# Wrap030_Memory.net
KiCad netlist of a schematic drawn in EAGLE
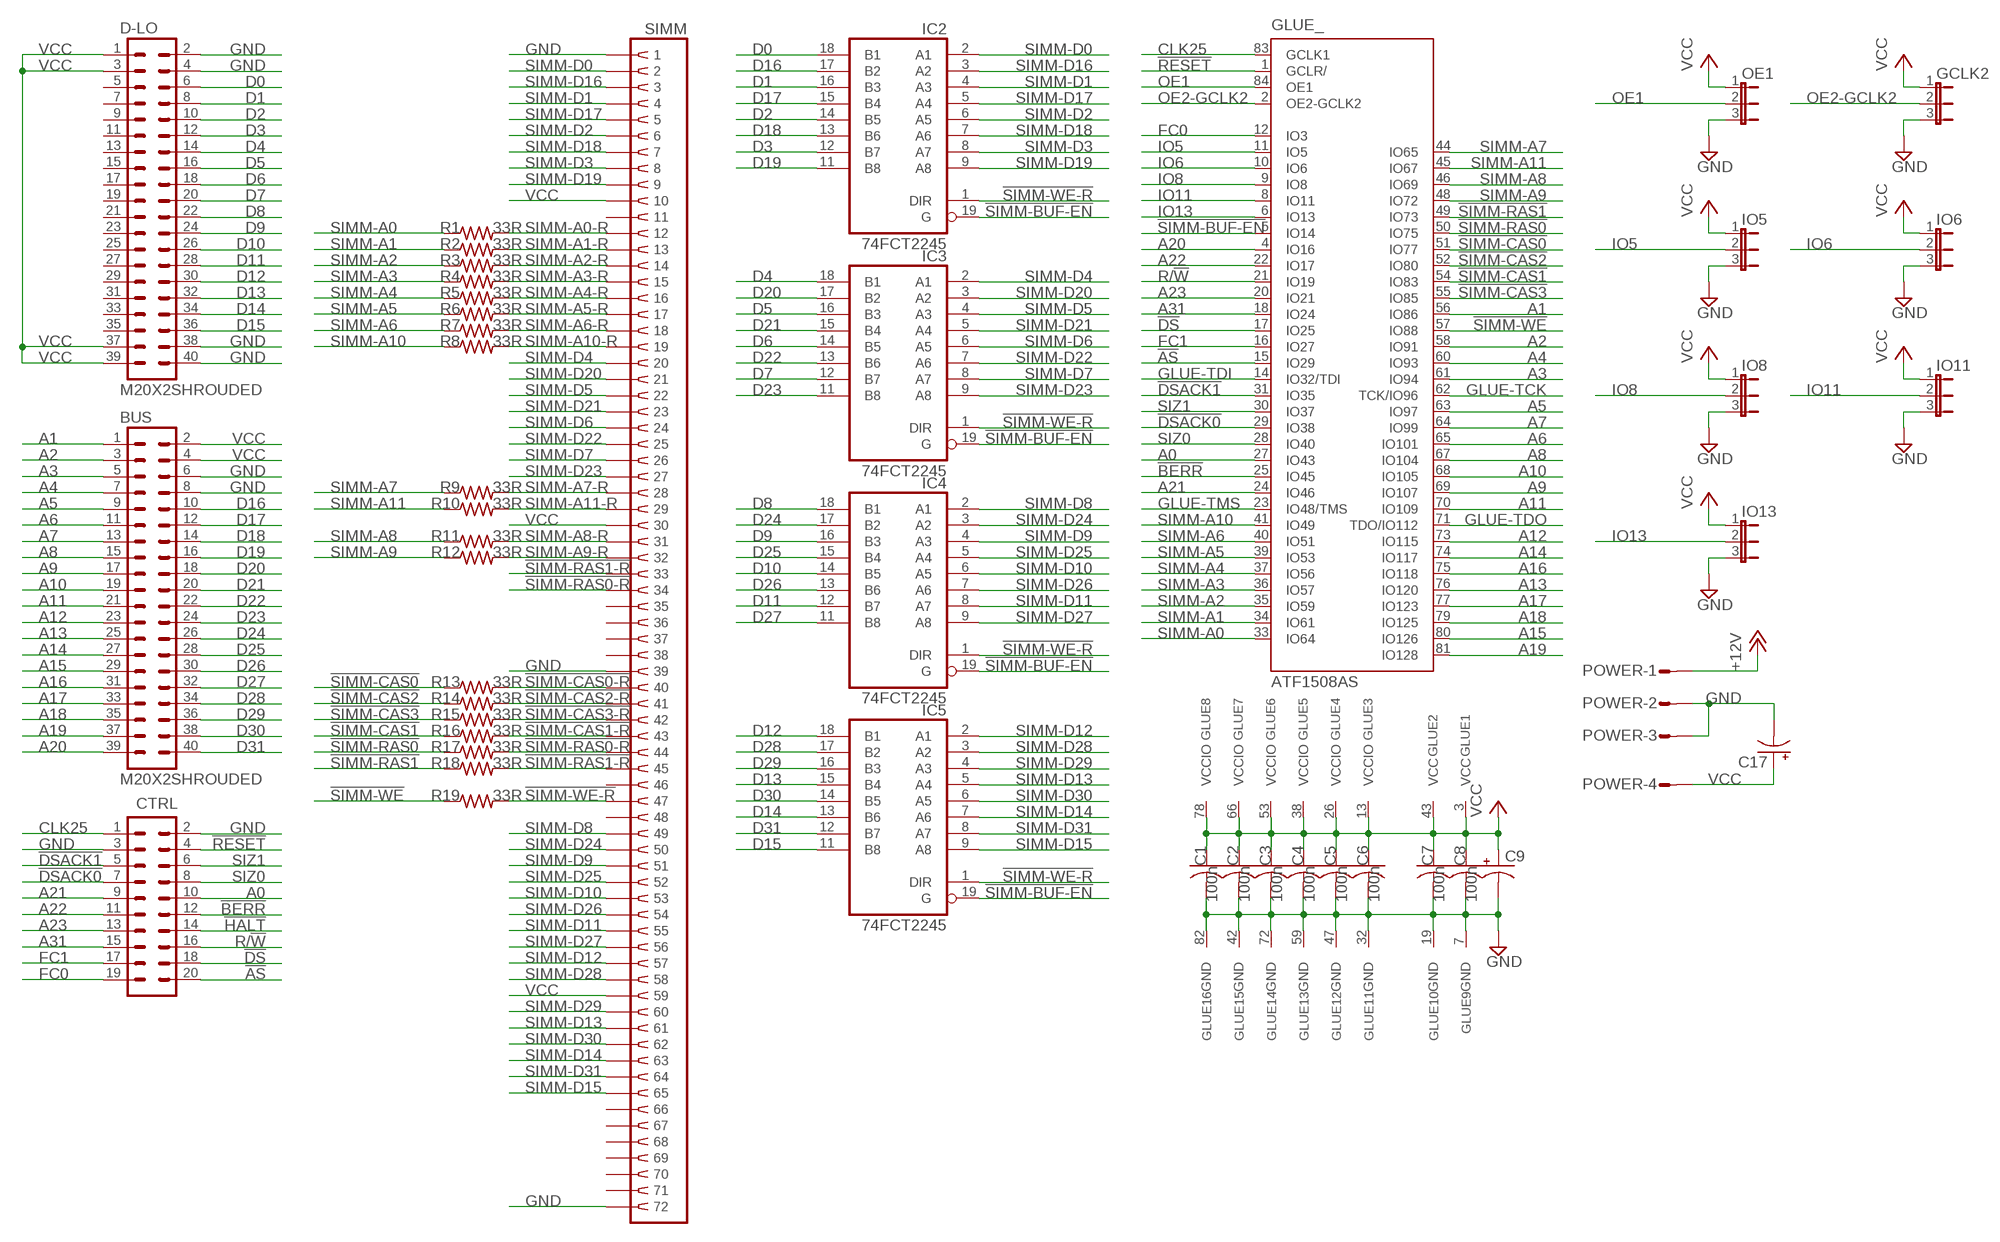
[diagram p0: schematic, sheet 1]

(export (version "E")
  (design (tool "Eeschema 10.0.6"))
  (components
    (comp (ref "BUS")
      (value "M20X2SHROUDED")
      (footprint "eagle-import:2X20_SHROUDED")
      (libsource (lib "eagle-import") (part "M20X2SHROUDED"))
    )
    (comp (ref "C1")
      (value "100n")
      (footprint "eagle-import:C0805")
      (libsource (lib "eagle-import") (part "C-USC0805"))
    )
    (comp (ref "C2")
      (value "100n")
      (footprint "eagle-import:C0805")
      (libsource (lib "eagle-import") (part "C-USC0805"))
    )
    (comp (ref "C3")
      (value "100n")
      (footprint "eagle-import:C0805")
      (libsource (lib "eagle-import") (part "C-USC0805"))
    )
    (comp (ref "C4")
      (value "100n")
      (footprint "eagle-import:C0805")
      (libsource (lib "eagle-import") (part "C-USC0805"))
    )
    (comp (ref "C5")
      (value "100n")
      (footprint "eagle-import:C0805")
      (libsource (lib "eagle-import") (part "C-USC0805"))
    )
    (comp (ref "C6")
      (value "100n")
      (footprint "eagle-import:C0805")
      (libsource (lib "eagle-import") (part "C-USC0805"))
    )
    (comp (ref "C7")
      (value "100n")
      (footprint "eagle-import:C0805")
      (libsource (lib "eagle-import") (part "C-USC0805"))
    )
    (comp (ref "C8")
      (value "100n")
      (footprint "eagle-import:C0805")
      (libsource (lib "eagle-import") (part "C-USC0805"))
    )
    (comp (ref "C9")
      (value "CPOL-USE2-5")
      (footprint "eagle-import:E2-5")
      (libsource (lib "eagle-import") (part "CPOL-USE2-5"))
    )
    (comp (ref "C17")
      (value "CPOL-USE3.5-8")
      (footprint "eagle-import:E3,5-8")
      (libsource (lib "eagle-import") (part "CPOL-USE3.5-8"))
    )
    (comp (ref "CTRL")
      (value "M10X2")
      (footprint "eagle-import:2X10")
      (libsource (lib "eagle-import") (part "M10X2"))
    )
    (comp (ref "D-LO")
      (value "M20X2SHROUDED")
      (footprint "eagle-import:2X20_SHROUDED")
      (libsource (lib "eagle-import") (part "M20X2SHROUDED"))
    )
    (comp (ref "GCLK2")
      (value "JP2E")
      (footprint "eagle-import:JP2")
      (libsource (lib "eagle-import") (part "JP2E"))
    )
    (comp (ref "GLUE")
      (value "ATF1508AS")
      (footprint "eagle-import:S84")
      (libsource (lib "eagle-import") (part "EPM7128-J84S"))
    )
    (comp (ref "IC2")
      (value "74FCT2245")
      (footprint "eagle-import:SO20W")
      (libsource (lib "eagle-import") (part "74245DWLS"))
    )
    (comp (ref "IC3")
      (value "74FCT2245")
      (footprint "eagle-import:SO20W")
      (libsource (lib "eagle-import") (part "74245DWLS"))
    )
    (comp (ref "IC4")
      (value "74FCT2245")
      (footprint "eagle-import:SO20W")
      (libsource (lib "eagle-import") (part "74245DWLS"))
    )
    (comp (ref "IC5")
      (value "74FCT2245")
      (footprint "eagle-import:SO20W")
      (libsource (lib "eagle-import") (part "74245DWLS"))
    )
    (comp (ref "IO5")
      (value "JP2E")
      (footprint "eagle-import:JP2")
      (libsource (lib "eagle-import") (part "JP2E"))
    )
    (comp (ref "IO6")
      (value "JP2E")
      (footprint "eagle-import:JP2")
      (libsource (lib "eagle-import") (part "JP2E"))
    )
    (comp (ref "IO8")
      (value "JP2E")
      (footprint "eagle-import:JP2")
      (libsource (lib "eagle-import") (part "JP2E"))
    )
    (comp (ref "IO11")
      (value "JP2E")
      (footprint "eagle-import:JP2")
      (libsource (lib "eagle-import") (part "JP2E"))
    )
    (comp (ref "IO13")
      (value "JP2E")
      (footprint "eagle-import:JP2")
      (libsource (lib "eagle-import") (part "JP2E"))
    )
    (comp (ref "OE1")
      (value "JP2E")
      (footprint "eagle-import:JP2")
      (libsource (lib "eagle-import") (part "JP2E"))
    )
    (comp (ref "POWER")
      (value "L04P")
      (footprint "eagle-import:L04P")
      (libsource (lib "eagle-import") (part "L04P"))
    )
    (comp (ref "R1")
      (value "33R")
      (footprint "eagle-import:R0805")
      (libsource (lib "eagle-import") (part "R-US_R0805"))
    )
    (comp (ref "R2")
      (value "33R")
      (footprint "eagle-import:R0805")
      (libsource (lib "eagle-import") (part "R-US_R0805"))
    )
    (comp (ref "R3")
      (value "33R")
      (footprint "eagle-import:R0805")
      (libsource (lib "eagle-import") (part "R-US_R0805"))
    )
    (comp (ref "R4")
      (value "33R")
      (footprint "eagle-import:R0805")
      (libsource (lib "eagle-import") (part "R-US_R0805"))
    )
    (comp (ref "R5")
      (value "33R")
      (footprint "eagle-import:R0805")
      (libsource (lib "eagle-import") (part "R-US_R0805"))
    )
    (comp (ref "R6")
      (value "33R")
      (footprint "eagle-import:R0805")
      (libsource (lib "eagle-import") (part "R-US_R0805"))
    )
    (comp (ref "R7")
      (value "33R")
      (footprint "eagle-import:R0805")
      (libsource (lib "eagle-import") (part "R-US_R0805"))
    )
    (comp (ref "R8")
      (value "33R")
      (footprint "eagle-import:R0805")
      (libsource (lib "eagle-import") (part "R-US_R0805"))
    )
    (comp (ref "R9")
      (value "33R")
      (footprint "eagle-import:R0805")
      (libsource (lib "eagle-import") (part "R-US_R0805"))
    )
    (comp (ref "R10")
      (value "33R")
      (footprint "eagle-import:R0805")
      (libsource (lib "eagle-import") (part "R-US_R0805"))
    )
    (comp (ref "R11")
      (value "33R")
      (footprint "eagle-import:R0805")
      (libsource (lib "eagle-import") (part "R-US_R0805"))
    )
    (comp (ref "R12")
      (value "33R")
      (footprint "eagle-import:R0805")
      (libsource (lib "eagle-import") (part "R-US_R0805"))
    )
    (comp (ref "R13")
      (value "33R")
      (footprint "eagle-import:R0805")
      (libsource (lib "eagle-import") (part "R-US_R0805"))
    )
    (comp (ref "R14")
      (value "33R")
      (footprint "eagle-import:R0805")
      (libsource (lib "eagle-import") (part "R-US_R0805"))
    )
    (comp (ref "R15")
      (value "33R")
      (footprint "eagle-import:R0805")
      (libsource (lib "eagle-import") (part "R-US_R0805"))
    )
    (comp (ref "R16")
      (value "33R")
      (footprint "eagle-import:R0805")
      (libsource (lib "eagle-import") (part "R-US_R0805"))
    )
    (comp (ref "R17")
      (value "33R")
      (footprint "eagle-import:R0805")
      (libsource (lib "eagle-import") (part "R-US_R0805"))
    )
    (comp (ref "R18")
      (value "33R")
      (footprint "eagle-import:R0805")
      (libsource (lib "eagle-import") (part "R-US_R0805"))
    )
    (comp (ref "R19")
      (value "33R")
      (footprint "eagle-import:R0805")
      (libsource (lib "eagle-import") (part "R-US_R0805"))
    )
    (comp (ref "SIMM")
      (value "SIMM72")
      (footprint "eagle-import:73826962")
      (libsource (lib "eagle-import") (part "SIMM72"))
    )
  )
  (nets
    (net (code "1") (name "+12V") (class "Default")
      (node (ref "POWER") (pin "1") (pinfunction "S_1") (pintype "passive"))
    )
    (net (code "2") (name "/A0") (class "Default")
      (node (ref "CTRL") (pin "10") (pinfunction "10_10") (pintype "passive"))
      (node (ref "GLUE") (pin "27") (pinfunction "IO43_27") (pintype "bidirectional"))
    )
    (net (code "3") (name "/A1") (class "Default")
      (node (ref "BUS") (pin "1") (pinfunction "1_1") (pintype "passive"))
      (node (ref "GLUE") (pin "56") (pinfunction "IO86_56") (pintype "bidirectional"))
    )
    (net (code "4") (name "/A2") (class "Default")
      (node (ref "BUS") (pin "3") (pinfunction "3_3") (pintype "passive"))
      (node (ref "GLUE") (pin "58") (pinfunction "IO91_58") (pintype "bidirectional"))
    )
    (net (code "5") (name "/A3") (class "Default")
      (node (ref "BUS") (pin "5") (pinfunction "5_5") (pintype "passive"))
      (node (ref "GLUE") (pin "61") (pinfunction "IO94_61") (pintype "bidirectional"))
    )
    (net (code "6") (name "/A4") (class "Default")
      (node (ref "BUS") (pin "7") (pinfunction "7_7") (pintype "passive"))
      (node (ref "GLUE") (pin "60") (pinfunction "IO93_60") (pintype "bidirectional"))
    )
    (net (code "7") (name "/A5") (class "Default")
      (node (ref "BUS") (pin "9") (pinfunction "9_9") (pintype "passive"))
      (node (ref "GLUE") (pin "63") (pinfunction "IO97_63") (pintype "bidirectional"))
    )
    (net (code "8") (name "/A6") (class "Default")
      (node (ref "BUS") (pin "11") (pinfunction "11_11") (pintype "passive"))
      (node (ref "GLUE") (pin "65") (pinfunction "IO101_65") (pintype "bidirectional"))
    )
    (net (code "9") (name "/A7") (class "Default")
      (node (ref "BUS") (pin "13") (pinfunction "13_13") (pintype "passive"))
      (node (ref "GLUE") (pin "64") (pinfunction "IO99_64") (pintype "bidirectional"))
    )
    (net (code "10") (name "/A8") (class "Default")
      (node (ref "BUS") (pin "15") (pinfunction "15_15") (pintype "passive"))
      (node (ref "GLUE") (pin "67") (pinfunction "IO104_67") (pintype "bidirectional"))
    )
    (net (code "11") (name "/A9") (class "Default")
      (node (ref "BUS") (pin "17") (pinfunction "17_17") (pintype "passive"))
      (node (ref "GLUE") (pin "69") (pinfunction "IO107_69") (pintype "bidirectional"))
    )
    (net (code "12") (name "/A10") (class "Default")
      (node (ref "BUS") (pin "19") (pinfunction "19_19") (pintype "passive"))
      (node (ref "GLUE") (pin "68") (pinfunction "IO105_68") (pintype "bidirectional"))
    )
    (net (code "13") (name "/A11") (class "Default")
      (node (ref "BUS") (pin "21") (pinfunction "21_21") (pintype "passive"))
      (node (ref "GLUE") (pin "70") (pinfunction "IO109_70") (pintype "bidirectional"))
    )
    (net (code "14") (name "/A12") (class "Default")
      (node (ref "BUS") (pin "23") (pinfunction "23_23") (pintype "passive"))
      (node (ref "GLUE") (pin "73") (pinfunction "IO115_73") (pintype "bidirectional"))
    )
    (net (code "15") (name "/A13") (class "Default")
      (node (ref "BUS") (pin "25") (pinfunction "25_25") (pintype "passive"))
      (node (ref "GLUE") (pin "76") (pinfunction "IO120_76") (pintype "bidirectional"))
    )
    (net (code "16") (name "/A14") (class "Default")
      (node (ref "BUS") (pin "27") (pinfunction "27_27") (pintype "passive"))
      (node (ref "GLUE") (pin "74") (pinfunction "IO117_74") (pintype "bidirectional"))
    )
    (net (code "17") (name "/A15") (class "Default")
      (node (ref "BUS") (pin "29") (pinfunction "29_29") (pintype "passive"))
      (node (ref "GLUE") (pin "80") (pinfunction "IO126_80") (pintype "bidirectional"))
    )
    (net (code "18") (name "/A16") (class "Default")
      (node (ref "BUS") (pin "31") (pinfunction "31_31") (pintype "passive"))
      (node (ref "GLUE") (pin "75") (pinfunction "IO118_75") (pintype "bidirectional"))
    )
    (net (code "19") (name "/A17") (class "Default")
      (node (ref "BUS") (pin "33") (pinfunction "33_33") (pintype "passive"))
      (node (ref "GLUE") (pin "77") (pinfunction "IO123_77") (pintype "bidirectional"))
    )
    (net (code "20") (name "/A18") (class "Default")
      (node (ref "BUS") (pin "35") (pinfunction "35_35") (pintype "passive"))
      (node (ref "GLUE") (pin "79") (pinfunction "IO125_79") (pintype "bidirectional"))
    )
    (net (code "21") (name "/A19") (class "Default")
      (node (ref "BUS") (pin "37") (pinfunction "37_37") (pintype "passive"))
      (node (ref "GLUE") (pin "81") (pinfunction "IO128_81") (pintype "bidirectional"))
    )
    (net (code "22") (name "/A20") (class "Default")
      (node (ref "BUS") (pin "39") (pinfunction "39_39") (pintype "passive"))
      (node (ref "GLUE") (pin "4") (pinfunction "IO16_4") (pintype "bidirectional"))
    )
    (net (code "23") (name "/A21") (class "Default")
      (node (ref "CTRL") (pin "9") (pinfunction "9_9") (pintype "passive"))
      (node (ref "GLUE") (pin "24") (pinfunction "IO46_24") (pintype "bidirectional"))
    )
    (net (code "24") (name "/A22") (class "Default")
      (node (ref "CTRL") (pin "11") (pinfunction "11_11") (pintype "passive"))
      (node (ref "GLUE") (pin "22") (pinfunction "IO17_22") (pintype "bidirectional"))
    )
    (net (code "25") (name "/A23") (class "Default")
      (node (ref "CTRL") (pin "13") (pinfunction "13_13") (pintype "passive"))
      (node (ref "GLUE") (pin "20") (pinfunction "IO21_20") (pintype "bidirectional"))
    )
    (net (code "26") (name "/A31") (class "Default")
      (node (ref "CTRL") (pin "15") (pinfunction "15_15") (pintype "passive"))
      (node (ref "GLUE") (pin "18") (pinfunction "IO24_18") (pintype "bidirectional"))
    )
    (net (code "27") (name "/CLK25") (class "Default")
      (node (ref "CTRL") (pin "1") (pinfunction "1_1") (pintype "passive"))
      (node (ref "GLUE") (pin "83") (pinfunction "GCLK1_83") (pintype "input"))
    )
    (net (code "28") (name "/D0") (class "Default")
      (node (ref "D-LO") (pin "6") (pinfunction "6_6") (pintype "passive"))
      (node (ref "IC2") (pin "18") (pinfunction "B1_18") (pintype "bidirectional"))
    )
    (net (code "29") (name "/D1") (class "Default")
      (node (ref "D-LO") (pin "8") (pinfunction "8_8") (pintype "passive"))
      (node (ref "IC2") (pin "16") (pinfunction "B3_16") (pintype "bidirectional"))
    )
    (net (code "30") (name "/D2") (class "Default")
      (node (ref "D-LO") (pin "10") (pinfunction "10_10") (pintype "passive"))
      (node (ref "IC2") (pin "14") (pinfunction "B5_14") (pintype "bidirectional"))
    )
    (net (code "31") (name "/D3") (class "Default")
      (node (ref "D-LO") (pin "12") (pinfunction "12_12") (pintype "passive"))
      (node (ref "IC2") (pin "12") (pinfunction "B7_12") (pintype "bidirectional"))
    )
    (net (code "32") (name "/D4") (class "Default")
      (node (ref "D-LO") (pin "14") (pinfunction "14_14") (pintype "passive"))
      (node (ref "IC3") (pin "18") (pinfunction "B1_18") (pintype "bidirectional"))
    )
    (net (code "33") (name "/D5") (class "Default")
      (node (ref "D-LO") (pin "16") (pinfunction "16_16") (pintype "passive"))
      (node (ref "IC3") (pin "16") (pinfunction "B3_16") (pintype "bidirectional"))
    )
    (net (code "34") (name "/D6") (class "Default")
      (node (ref "D-LO") (pin "18") (pinfunction "18_18") (pintype "passive"))
      (node (ref "IC3") (pin "14") (pinfunction "B5_14") (pintype "bidirectional"))
    )
    (net (code "35") (name "/D7") (class "Default")
      (node (ref "D-LO") (pin "20") (pinfunction "20_20") (pintype "passive"))
      (node (ref "IC3") (pin "12") (pinfunction "B7_12") (pintype "bidirectional"))
    )
    (net (code "36") (name "/D8") (class "Default")
      (node (ref "D-LO") (pin "22") (pinfunction "22_22") (pintype "passive"))
      (node (ref "IC4") (pin "18") (pinfunction "B1_18") (pintype "bidirectional"))
    )
    (net (code "37") (name "/D9") (class "Default")
      (node (ref "D-LO") (pin "24") (pinfunction "24_24") (pintype "passive"))
      (node (ref "IC4") (pin "16") (pinfunction "B3_16") (pintype "bidirectional"))
    )
    (net (code "38") (name "/D10") (class "Default")
      (node (ref "D-LO") (pin "26") (pinfunction "26_26") (pintype "passive"))
      (node (ref "IC4") (pin "14") (pinfunction "B5_14") (pintype "bidirectional"))
    )
    (net (code "39") (name "/D11") (class "Default")
      (node (ref "D-LO") (pin "28") (pinfunction "28_28") (pintype "passive"))
      (node (ref "IC4") (pin "12") (pinfunction "B7_12") (pintype "bidirectional"))
    )
    (net (code "40") (name "/D12") (class "Default")
      (node (ref "D-LO") (pin "30") (pinfunction "30_30") (pintype "passive"))
      (node (ref "IC5") (pin "18") (pinfunction "B1_18") (pintype "bidirectional"))
    )
    (net (code "41") (name "/D13") (class "Default")
      (node (ref "D-LO") (pin "32") (pinfunction "32_32") (pintype "passive"))
      (node (ref "IC5") (pin "15") (pinfunction "B4_15") (pintype "bidirectional"))
    )
    (net (code "42") (name "/D14") (class "Default")
      (node (ref "D-LO") (pin "34") (pinfunction "34_34") (pintype "passive"))
      (node (ref "IC5") (pin "13") (pinfunction "B6_13") (pintype "bidirectional"))
    )
    (net (code "43") (name "/D15") (class "Default")
      (node (ref "D-LO") (pin "36") (pinfunction "36_36") (pintype "passive"))
      (node (ref "IC5") (pin "11") (pinfunction "B8_11") (pintype "bidirectional"))
    )
    (net (code "44") (name "/D16") (class "Default")
      (node (ref "BUS") (pin "10") (pinfunction "10_10") (pintype "passive"))
      (node (ref "IC2") (pin "17") (pinfunction "B2_17") (pintype "bidirectional"))
    )
    (net (code "45") (name "/D17") (class "Default")
      (node (ref "BUS") (pin "12") (pinfunction "12_12") (pintype "passive"))
      (node (ref "IC2") (pin "15") (pinfunction "B4_15") (pintype "bidirectional"))
    )
    (net (code "46") (name "/D18") (class "Default")
      (node (ref "BUS") (pin "14") (pinfunction "14_14") (pintype "passive"))
      (node (ref "IC2") (pin "13") (pinfunction "B6_13") (pintype "bidirectional"))
    )
    (net (code "47") (name "/D19") (class "Default")
      (node (ref "BUS") (pin "16") (pinfunction "16_16") (pintype "passive"))
      (node (ref "IC2") (pin "11") (pinfunction "B8_11") (pintype "bidirectional"))
    )
    (net (code "48") (name "/D20") (class "Default")
      (node (ref "BUS") (pin "18") (pinfunction "18_18") (pintype "passive"))
      (node (ref "IC3") (pin "17") (pinfunction "B2_17") (pintype "bidirectional"))
    )
    (net (code "49") (name "/D21") (class "Default")
      (node (ref "BUS") (pin "20") (pinfunction "20_20") (pintype "passive"))
      (node (ref "IC3") (pin "15") (pinfunction "B4_15") (pintype "bidirectional"))
    )
    (net (code "50") (name "/D22") (class "Default")
      (node (ref "BUS") (pin "22") (pinfunction "22_22") (pintype "passive"))
      (node (ref "IC3") (pin "13") (pinfunction "B6_13") (pintype "bidirectional"))
    )
    (net (code "51") (name "/D23") (class "Default")
      (node (ref "BUS") (pin "24") (pinfunction "24_24") (pintype "passive"))
      (node (ref "IC3") (pin "11") (pinfunction "B8_11") (pintype "bidirectional"))
    )
    (net (code "52") (name "/D24") (class "Default")
      (node (ref "BUS") (pin "26") (pinfunction "26_26") (pintype "passive"))
      (node (ref "IC4") (pin "17") (pinfunction "B2_17") (pintype "bidirectional"))
    )
    (net (code "53") (name "/D25") (class "Default")
      (node (ref "BUS") (pin "28") (pinfunction "28_28") (pintype "passive"))
      (node (ref "IC4") (pin "15") (pinfunction "B4_15") (pintype "bidirectional"))
    )
    (net (code "54") (name "/D26") (class "Default")
      (node (ref "BUS") (pin "30") (pinfunction "30_30") (pintype "passive"))
      (node (ref "IC4") (pin "13") (pinfunction "B6_13") (pintype "bidirectional"))
    )
    (net (code "55") (name "/D27") (class "Default")
      (node (ref "BUS") (pin "32") (pinfunction "32_32") (pintype "passive"))
      (node (ref "IC4") (pin "11") (pinfunction "B8_11") (pintype "bidirectional"))
    )
    (net (code "56") (name "/D28") (class "Default")
      (node (ref "BUS") (pin "34") (pinfunction "34_34") (pintype "passive"))
      (node (ref "IC5") (pin "17") (pinfunction "B2_17") (pintype "bidirectional"))
    )
    (net (code "57") (name "/D29") (class "Default")
      (node (ref "BUS") (pin "36") (pinfunction "36_36") (pintype "passive"))
      (node (ref "IC5") (pin "16") (pinfunction "B3_16") (pintype "bidirectional"))
    )
    (net (code "58") (name "/D30") (class "Default")
      (node (ref "BUS") (pin "38") (pinfunction "38_38") (pintype "passive"))
      (node (ref "IC5") (pin "14") (pinfunction "B5_14") (pintype "bidirectional"))
    )
    (net (code "59") (name "/D31") (class "Default")
      (node (ref "BUS") (pin "40") (pinfunction "40_40") (pintype "passive"))
      (node (ref "IC5") (pin "12") (pinfunction "B7_12") (pintype "bidirectional"))
    )
    (net (code "60") (name "/FC0") (class "Default")
      (node (ref "CTRL") (pin "19") (pinfunction "19_19") (pintype "passive"))
      (node (ref "GLUE") (pin "12") (pinfunction "IO3_12") (pintype "bidirectional"))
    )
    (net (code "61") (name "/FC1") (class "Default")
      (node (ref "CTRL") (pin "17") (pinfunction "17_17") (pintype "passive"))
      (node (ref "GLUE") (pin "16") (pinfunction "IO27_16") (pintype "bidirectional"))
    )
    (net (code "62") (name "/GLUE-TCK") (class "Default")
      (node (ref "GLUE") (pin "62") (pinfunction "TCK/IO96_62") (pintype "bidirectional"))
    )
    (net (code "63") (name "/GLUE-TDI") (class "Default")
      (node (ref "GLUE") (pin "14") (pinfunction "IO32/TDI_14") (pintype "bidirectional"))
    )
    (net (code "64") (name "/GLUE-TDO") (class "Default")
      (node (ref "GLUE") (pin "71") (pinfunction "TDO/IO112_71") (pintype "bidirectional"))
    )
    (net (code "65") (name "/GLUE-TMS") (class "Default")
      (node (ref "GLUE") (pin "23") (pinfunction "IO48/TMS_23") (pintype "bidirectional"))
    )
    (net (code "66") (name "/IO5") (class "Default")
      (node (ref "GLUE") (pin "11") (pinfunction "IO5_11") (pintype "bidirectional"))
      (node (ref "IO5") (pin "2") (pinfunction "2_2") (pintype "passive"))
    )
    (net (code "67") (name "/IO6") (class "Default")
      (node (ref "GLUE") (pin "10") (pinfunction "IO6_10") (pintype "bidirectional"))
      (node (ref "IO6") (pin "2") (pinfunction "2_2") (pintype "passive"))
    )
    (net (code "68") (name "/IO8") (class "Default")
      (node (ref "GLUE") (pin "9") (pinfunction "IO8_9") (pintype "bidirectional"))
      (node (ref "IO8") (pin "2") (pinfunction "2_2") (pintype "passive"))
    )
    (net (code "69") (name "/IO11") (class "Default")
      (node (ref "GLUE") (pin "8") (pinfunction "IO11_8") (pintype "bidirectional"))
      (node (ref "IO11") (pin "2") (pinfunction "2_2") (pintype "passive"))
    )
    (net (code "70") (name "/IO13") (class "Default")
      (node (ref "GLUE") (pin "6") (pinfunction "IO13_6") (pintype "bidirectional"))
      (node (ref "IO13") (pin "2") (pinfunction "2_2") (pintype "passive"))
    )
    (net (code "71") (name "/OE1") (class "Default")
      (node (ref "GLUE") (pin "84") (pinfunction "OE1_84") (pintype "input"))
      (node (ref "OE1") (pin "2") (pinfunction "2_2") (pintype "passive"))
    )
    (net (code "72") (name "/OE2-GCLK2") (class "Default")
      (node (ref "GCLK2") (pin "2") (pinfunction "2_2") (pintype "passive"))
      (node (ref "GLUE") (pin "2") (pinfunction "OE2-GCLK2_2") (pintype "input"))
    )
    (net (code "73") (name "/R{slash}~{W}") (class "Default")
      (node (ref "CTRL") (pin "16") (pinfunction "16_16") (pintype "passive"))
      (node (ref "GLUE") (pin "21") (pinfunction "IO19_21") (pintype "bidirectional"))
    )
    (net (code "74") (name "/SIMM-A0") (class "Default")
      (node (ref "GLUE") (pin "33") (pinfunction "IO64_33") (pintype "bidirectional"))
      (node (ref "R1") (pin "1") (pinfunction "1_1") (pintype "passive"))
    )
    (net (code "75") (name "/SIMM-A0-R") (class "Default")
      (node (ref "R1") (pin "2") (pinfunction "2_2") (pintype "passive"))
      (node (ref "SIMM") (pin "12") (pinfunction "12_12") (pintype "passive"))
    )
    (net (code "76") (name "/SIMM-A1") (class "Default")
      (node (ref "GLUE") (pin "34") (pinfunction "IO61_34") (pintype "bidirectional"))
      (node (ref "R2") (pin "1") (pinfunction "1_1") (pintype "passive"))
    )
    (net (code "77") (name "/SIMM-A1-R") (class "Default")
      (node (ref "R2") (pin "2") (pinfunction "2_2") (pintype "passive"))
      (node (ref "SIMM") (pin "13") (pinfunction "13_13") (pintype "passive"))
    )
    (net (code "78") (name "/SIMM-A2") (class "Default")
      (node (ref "GLUE") (pin "35") (pinfunction "IO59_35") (pintype "bidirectional"))
      (node (ref "R3") (pin "1") (pinfunction "1_1") (pintype "passive"))
    )
    (net (code "79") (name "/SIMM-A2-R") (class "Default")
      (node (ref "R3") (pin "2") (pinfunction "2_2") (pintype "passive"))
      (node (ref "SIMM") (pin "14") (pinfunction "14_14") (pintype "passive"))
    )
    (net (code "80") (name "/SIMM-A3") (class "Default")
      (node (ref "GLUE") (pin "36") (pinfunction "IO57_36") (pintype "bidirectional"))
      (node (ref "R4") (pin "1") (pinfunction "1_1") (pintype "passive"))
    )
    (net (code "81") (name "/SIMM-A3-R") (class "Default")
      (node (ref "R4") (pin "2") (pinfunction "2_2") (pintype "passive"))
      (node (ref "SIMM") (pin "15") (pinfunction "15_15") (pintype "passive"))
    )
    (net (code "82") (name "/SIMM-A4") (class "Default")
      (node (ref "GLUE") (pin "37") (pinfunction "IO56_37") (pintype "bidirectional"))
      (node (ref "R5") (pin "1") (pinfunction "1_1") (pintype "passive"))
    )
    (net (code "83") (name "/SIMM-A4-R") (class "Default")
      (node (ref "R5") (pin "2") (pinfunction "2_2") (pintype "passive"))
      (node (ref "SIMM") (pin "16") (pinfunction "16_16") (pintype "passive"))
    )
    (net (code "84") (name "/SIMM-A5") (class "Default")
      (node (ref "GLUE") (pin "39") (pinfunction "IO53_39") (pintype "bidirectional"))
      (node (ref "R6") (pin "1") (pinfunction "1_1") (pintype "passive"))
    )
    (net (code "85") (name "/SIMM-A5-R") (class "Default")
      (node (ref "R6") (pin "2") (pinfunction "2_2") (pintype "passive"))
      (node (ref "SIMM") (pin "17") (pinfunction "17_17") (pintype "passive"))
    )
    (net (code "86") (name "/SIMM-A6") (class "Default")
      (node (ref "GLUE") (pin "40") (pinfunction "IO51_40") (pintype "bidirectional"))
      (node (ref "R7") (pin "1") (pinfunction "1_1") (pintype "passive"))
    )
    (net (code "87") (name "/SIMM-A6-R") (class "Default")
      (node (ref "R7") (pin "2") (pinfunction "2_2") (pintype "passive"))
      (node (ref "SIMM") (pin "18") (pinfunction "18_18") (pintype "passive"))
    )
    (net (code "88") (name "/SIMM-A7") (class "Default")
      (node (ref "GLUE") (pin "44") (pinfunction "IO65_44") (pintype "bidirectional"))
      (node (ref "R9") (pin "1") (pinfunction "1_1") (pintype "passive"))
    )
    (net (code "89") (name "/SIMM-A7-R") (class "Default")
      (node (ref "R9") (pin "2") (pinfunction "2_2") (pintype "passive"))
      (node (ref "SIMM") (pin "28") (pinfunction "28_28") (pintype "passive"))
    )
    (net (code "90") (name "/SIMM-A8") (class "Default")
      (node (ref "GLUE") (pin "46") (pinfunction "IO69_46") (pintype "bidirectional"))
      (node (ref "R11") (pin "1") (pinfunction "1_1") (pintype "passive"))
    )
    (net (code "91") (name "/SIMM-A8-R") (class "Default")
      (node (ref "R11") (pin "2") (pinfunction "2_2") (pintype "passive"))
      (node (ref "SIMM") (pin "31") (pinfunction "31_31") (pintype "passive"))
    )
    (net (code "92") (name "/SIMM-A9") (class "Default")
      (node (ref "GLUE") (pin "48") (pinfunction "IO72_48") (pintype "bidirectional"))
      (node (ref "R12") (pin "1") (pinfunction "1_1") (pintype "passive"))
    )
    (net (code "93") (name "/SIMM-A9-R") (class "Default")
      (node (ref "R12") (pin "2") (pinfunction "2_2") (pintype "passive"))
      (node (ref "SIMM") (pin "32") (pinfunction "32_32") (pintype "passive"))
    )
    (net (code "94") (name "/SIMM-A10") (class "Default")
      (node (ref "GLUE") (pin "41") (pinfunction "IO49_41") (pintype "bidirectional"))
      (node (ref "R8") (pin "1") (pinfunction "1_1") (pintype "passive"))
    )
    (net (code "95") (name "/SIMM-A10-R") (class "Default")
      (node (ref "R8") (pin "2") (pinfunction "2_2") (pintype "passive"))
      (node (ref "SIMM") (pin "19") (pinfunction "19_19") (pintype "passive"))
    )
    (net (code "96") (name "/SIMM-A11") (class "Default")
      (node (ref "GLUE") (pin "45") (pinfunction "IO67_45") (pintype "bidirectional"))
      (node (ref "R10") (pin "1") (pinfunction "1_1") (pintype "passive"))
    )
    (net (code "97") (name "/SIMM-A11-R") (class "Default")
      (node (ref "R10") (pin "2") (pinfunction "2_2") (pintype "passive"))
      (node (ref "SIMM") (pin "29") (pinfunction "29_29") (pintype "passive"))
    )
    (net (code "98") (name "/SIMM-D0") (class "Default")
      (node (ref "IC2") (pin "2") (pinfunction "A1_2") (pintype "bidirectional"))
      (node (ref "SIMM") (pin "2") (pinfunction "2_2") (pintype "passive"))
    )
    (net (code "99") (name "/SIMM-D1") (class "Default")
      (node (ref "IC2") (pin "4") (pinfunction "A3_4") (pintype "bidirectional"))
      (node (ref "SIMM") (pin "4") (pinfunction "4_4") (pintype "passive"))
    )
    (net (code "100") (name "/SIMM-D2") (class "Default")
      (node (ref "IC2") (pin "6") (pinfunction "A5_6") (pintype "bidirectional"))
      (node (ref "SIMM") (pin "6") (pinfunction "6_6") (pintype "passive"))
    )
    (net (code "101") (name "/SIMM-D3") (class "Default")
      (node (ref "IC2") (pin "8") (pinfunction "A7_8") (pintype "bidirectional"))
      (node (ref "SIMM") (pin "8") (pinfunction "8_8") (pintype "passive"))
    )
    (net (code "102") (name "/SIMM-D4") (class "Default")
      (node (ref "IC3") (pin "2") (pinfunction "A1_2") (pintype "bidirectional"))
      (node (ref "SIMM") (pin "20") (pinfunction "20_20") (pintype "passive"))
    )
    (net (code "103") (name "/SIMM-D5") (class "Default")
      (node (ref "IC3") (pin "4") (pinfunction "A3_4") (pintype "bidirectional"))
      (node (ref "SIMM") (pin "22") (pinfunction "22_22") (pintype "passive"))
    )
    (net (code "104") (name "/SIMM-D6") (class "Default")
      (node (ref "IC3") (pin "6") (pinfunction "A5_6") (pintype "bidirectional"))
      (node (ref "SIMM") (pin "24") (pinfunction "24_24") (pintype "passive"))
    )
    (net (code "105") (name "/SIMM-D7") (class "Default")
      (node (ref "IC3") (pin "8") (pinfunction "A7_8") (pintype "bidirectional"))
      (node (ref "SIMM") (pin "26") (pinfunction "26_26") (pintype "passive"))
    )
    (net (code "106") (name "/SIMM-D8") (class "Default")
      (node (ref "IC4") (pin "2") (pinfunction "A1_2") (pintype "bidirectional"))
      (node (ref "SIMM") (pin "49") (pinfunction "49_49") (pintype "passive"))
    )
    (net (code "107") (name "/SIMM-D9") (class "Default")
      (node (ref "IC4") (pin "4") (pinfunction "A3_4") (pintype "bidirectional"))
      (node (ref "SIMM") (pin "51") (pinfunction "51_51") (pintype "passive"))
    )
    (net (code "108") (name "/SIMM-D10") (class "Default")
      (node (ref "IC4") (pin "6") (pinfunction "A5_6") (pintype "bidirectional"))
      (node (ref "SIMM") (pin "53") (pinfunction "53_53") (pintype "passive"))
    )
    (net (code "109") (name "/SIMM-D11") (class "Default")
      (node (ref "IC4") (pin "8") (pinfunction "A7_8") (pintype "bidirectional"))
      (node (ref "SIMM") (pin "55") (pinfunction "55_55") (pintype "passive"))
    )
    (net (code "110") (name "/SIMM-D12") (class "Default")
      (node (ref "IC5") (pin "2") (pinfunction "A1_2") (pintype "bidirectional"))
      (node (ref "SIMM") (pin "57") (pinfunction "57_57") (pintype "passive"))
    )
    (net (code "111") (name "/SIMM-D13") (class "Default")
      (node (ref "IC5") (pin "5") (pinfunction "A4_5") (pintype "bidirectional"))
      (node (ref "SIMM") (pin "61") (pinfunction "61_61") (pintype "passive"))
    )
    (net (code "112") (name "/SIMM-D14") (class "Default")
      (node (ref "IC5") (pin "7") (pinfunction "A6_7") (pintype "bidirectional"))
      (node (ref "SIMM") (pin "63") (pinfunction "63_63") (pintype "passive"))
    )
    (net (code "113") (name "/SIMM-D15") (class "Default")
      (node (ref "IC5") (pin "9") (pinfunction "A8_9") (pintype "bidirectional"))
      (node (ref "SIMM") (pin "65") (pinfunction "65_65") (pintype "passive"))
    )
    (net (code "114") (name "/SIMM-D16") (class "Default")
      (node (ref "IC2") (pin "3") (pinfunction "A2_3") (pintype "bidirectional"))
      (node (ref "SIMM") (pin "3") (pinfunction "3_3") (pintype "passive"))
    )
    (net (code "115") (name "/SIMM-D17") (class "Default")
      (node (ref "IC2") (pin "5") (pinfunction "A4_5") (pintype "bidirectional"))
      (node (ref "SIMM") (pin "5") (pinfunction "5_5") (pintype "passive"))
    )
    (net (code "116") (name "/SIMM-D18") (class "Default")
      (node (ref "IC2") (pin "7") (pinfunction "A6_7") (pintype "bidirectional"))
      (node (ref "SIMM") (pin "7") (pinfunction "7_7") (pintype "passive"))
    )
    (net (code "117") (name "/SIMM-D19") (class "Default")
      (node (ref "IC2") (pin "9") (pinfunction "A8_9") (pintype "bidirectional"))
      (node (ref "SIMM") (pin "9") (pinfunction "9_9") (pintype "passive"))
    )
    (net (code "118") (name "/SIMM-D20") (class "Default")
      (node (ref "IC3") (pin "3") (pinfunction "A2_3") (pintype "bidirectional"))
      (node (ref "SIMM") (pin "21") (pinfunction "21_21") (pintype "passive"))
    )
    (net (code "119") (name "/SIMM-D21") (class "Default")
      (node (ref "IC3") (pin "5") (pinfunction "A4_5") (pintype "bidirectional"))
      (node (ref "SIMM") (pin "23") (pinfunction "23_23") (pintype "passive"))
    )
    (net (code "120") (name "/SIMM-D22") (class "Default")
      (node (ref "IC3") (pin "7") (pinfunction "A6_7") (pintype "bidirectional"))
      (node (ref "SIMM") (pin "25") (pinfunction "25_25") (pintype "passive"))
    )
    (net (code "121") (name "/SIMM-D23") (class "Default")
      (node (ref "IC3") (pin "9") (pinfunction "A8_9") (pintype "bidirectional"))
      (node (ref "SIMM") (pin "27") (pinfunction "27_27") (pintype "passive"))
    )
    (net (code "122") (name "/SIMM-D24") (class "Default")
      (node (ref "IC4") (pin "3") (pinfunction "A2_3") (pintype "bidirectional"))
      (node (ref "SIMM") (pin "50") (pinfunction "50_50") (pintype "passive"))
    )
    (net (code "123") (name "/SIMM-D25") (class "Default")
      (node (ref "IC4") (pin "5") (pinfunction "A4_5") (pintype "bidirectional"))
      (node (ref "SIMM") (pin "52") (pinfunction "52_52") (pintype "passive"))
    )
    (net (code "124") (name "/SIMM-D26") (class "Default")
      (node (ref "IC4") (pin "7") (pinfunction "A6_7") (pintype "bidirectional"))
      (node (ref "SIMM") (pin "54") (pinfunction "54_54") (pintype "passive"))
    )
    (net (code "125") (name "/SIMM-D27") (class "Default")
      (node (ref "IC4") (pin "9") (pinfunction "A8_9") (pintype "bidirectional"))
      (node (ref "SIMM") (pin "56") (pinfunction "56_56") (pintype "passive"))
    )
    (net (code "126") (name "/SIMM-D28") (class "Default")
      (node (ref "IC5") (pin "3") (pinfunction "A2_3") (pintype "bidirectional"))
      (node (ref "SIMM") (pin "58") (pinfunction "58_58") (pintype "passive"))
    )
    (net (code "127") (name "/SIMM-D29") (class "Default")
      (node (ref "IC5") (pin "4") (pinfunction "A3_4") (pintype "bidirectional"))
      (node (ref "SIMM") (pin "60") (pinfunction "60_60") (pintype "passive"))
    )
    (net (code "128") (name "/SIMM-D30") (class "Default")
      (node (ref "IC5") (pin "6") (pinfunction "A5_6") (pintype "bidirectional"))
      (node (ref "SIMM") (pin "62") (pinfunction "62_62") (pintype "passive"))
    )
    (net (code "129") (name "/SIMM-D31") (class "Default")
      (node (ref "IC5") (pin "8") (pinfunction "A7_8") (pintype "bidirectional"))
      (node (ref "SIMM") (pin "64") (pinfunction "64_64") (pintype "passive"))
    )
    (net (code "130") (name "/SIZ0") (class "Default")
      (node (ref "CTRL") (pin "8") (pinfunction "8_8") (pintype "passive"))
      (node (ref "GLUE") (pin "28") (pinfunction "IO40_28") (pintype "bidirectional"))
    )
    (net (code "131") (name "/SIZ1") (class "Default")
      (node (ref "CTRL") (pin "6") (pinfunction "6_6") (pintype "passive"))
      (node (ref "GLUE") (pin "30") (pinfunction "IO37_30") (pintype "bidirectional"))
    )
    (net (code "132") (name "/~{AS}") (class "Default")
      (node (ref "CTRL") (pin "20") (pinfunction "20_20") (pintype "passive"))
      (node (ref "GLUE") (pin "15") (pinfunction "IO29_15") (pintype "bidirectional"))
    )
    (net (code "133") (name "/~{BERR}") (class "Default")
      (node (ref "CTRL") (pin "12") (pinfunction "12_12") (pintype "passive"))
      (node (ref "GLUE") (pin "25") (pinfunction "IO45_25") (pintype "bidirectional"))
    )
    (net (code "134") (name "/~{DSACK0}") (class "Default")
      (node (ref "CTRL") (pin "7") (pinfunction "7_7") (pintype "passive"))
      (node (ref "GLUE") (pin "29") (pinfunction "IO38_29") (pintype "bidirectional"))
    )
    (net (code "135") (name "/~{DSACK1}") (class "Default")
      (node (ref "CTRL") (pin "5") (pinfunction "5_5") (pintype "passive"))
      (node (ref "GLUE") (pin "31") (pinfunction "IO35_31") (pintype "bidirectional"))
    )
    (net (code "136") (name "/~{DS}") (class "Default")
      (node (ref "CTRL") (pin "18") (pinfunction "18_18") (pintype "passive"))
      (node (ref "GLUE") (pin "17") (pinfunction "IO25_17") (pintype "bidirectional"))
    )
    (net (code "137") (name "/~{HALT}") (class "Default")
      (node (ref "CTRL") (pin "14") (pinfunction "14_14") (pintype "passive"))
    )
    (net (code "138") (name "/~{RESET}") (class "Default")
      (node (ref "CTRL") (pin "4") (pinfunction "4_4") (pintype "passive"))
      (node (ref "GLUE") (pin "1") (pinfunction "GCLR/_1") (pintype "input"))
    )
    (net (code "139") (name "/~{SIMM-BUF-EN}") (class "Default")
      (node (ref "GLUE") (pin "5") (pinfunction "IO14_5") (pintype "bidirectional"))
      (node (ref "IC2") (pin "19") (pinfunction "G_19") (pintype "input"))
      (node (ref "IC3") (pin "19") (pinfunction "G_19") (pintype "input"))
      (node (ref "IC4") (pin "19") (pinfunction "G_19") (pintype "input"))
      (node (ref "IC5") (pin "19") (pinfunction "G_19") (pintype "input"))
    )
    (net (code "140") (name "/~{SIMM-CAS0-R}") (class "Default")
      (node (ref "R13") (pin "2") (pinfunction "2_2") (pintype "passive"))
      (node (ref "SIMM") (pin "40") (pinfunction "40_40") (pintype "passive"))
    )
    (net (code "141") (name "/~{SIMM-CAS0}") (class "Default")
      (node (ref "GLUE") (pin "51") (pinfunction "IO77_51") (pintype "bidirectional"))
      (node (ref "R13") (pin "1") (pinfunction "1_1") (pintype "passive"))
    )
    (net (code "142") (name "/~{SIMM-CAS1-R}") (class "Default")
      (node (ref "R16") (pin "2") (pinfunction "2_2") (pintype "passive"))
      (node (ref "SIMM") (pin "43") (pinfunction "43_43") (pintype "passive"))
    )
    (net (code "143") (name "/~{SIMM-CAS1}") (class "Default")
      (node (ref "GLUE") (pin "54") (pinfunction "IO83_54") (pintype "bidirectional"))
      (node (ref "R16") (pin "1") (pinfunction "1_1") (pintype "passive"))
    )
    (net (code "144") (name "/~{SIMM-CAS2-R}") (class "Default")
      (node (ref "R14") (pin "2") (pinfunction "2_2") (pintype "passive"))
      (node (ref "SIMM") (pin "41") (pinfunction "41_41") (pintype "passive"))
    )
    (net (code "145") (name "/~{SIMM-CAS2}") (class "Default")
      (node (ref "GLUE") (pin "52") (pinfunction "IO80_52") (pintype "bidirectional"))
      (node (ref "R14") (pin "1") (pinfunction "1_1") (pintype "passive"))
    )
    (net (code "146") (name "/~{SIMM-CAS3-R}") (class "Default")
      (node (ref "R15") (pin "2") (pinfunction "2_2") (pintype "passive"))
      (node (ref "SIMM") (pin "42") (pinfunction "42_42") (pintype "passive"))
    )
    (net (code "147") (name "/~{SIMM-CAS3}") (class "Default")
      (node (ref "GLUE") (pin "55") (pinfunction "IO85_55") (pintype "bidirectional"))
      (node (ref "R15") (pin "1") (pinfunction "1_1") (pintype "passive"))
    )
    (net (code "148") (name "/~{SIMM-RAS0-R}") (class "Default")
      (node (ref "R17") (pin "2") (pinfunction "2_2") (pintype "passive"))
      (node (ref "SIMM") (pin "34") (pinfunction "34_34") (pintype "passive"))
      (node (ref "SIMM") (pin "44") (pinfunction "44_44") (pintype "passive"))
    )
    (net (code "149") (name "/~{SIMM-RAS0}") (class "Default")
      (node (ref "GLUE") (pin "50") (pinfunction "IO75_50") (pintype "bidirectional"))
      (node (ref "R17") (pin "1") (pinfunction "1_1") (pintype "passive"))
    )
    (net (code "150") (name "/~{SIMM-RAS1-R}") (class "Default")
      (node (ref "R18") (pin "2") (pinfunction "2_2") (pintype "passive"))
      (node (ref "SIMM") (pin "33") (pinfunction "33_33") (pintype "passive"))
      (node (ref "SIMM") (pin "45") (pinfunction "45_45") (pintype "passive"))
    )
    (net (code "151") (name "/~{SIMM-RAS1}") (class "Default")
      (node (ref "GLUE") (pin "49") (pinfunction "IO73_49") (pintype "bidirectional"))
      (node (ref "R18") (pin "1") (pinfunction "1_1") (pintype "passive"))
    )
    (net (code "152") (name "/~{SIMM-WE-R}") (class "Default")
      (node (ref "IC2") (pin "1") (pinfunction "DIR_1") (pintype "input"))
      (node (ref "IC3") (pin "1") (pinfunction "DIR_1") (pintype "input"))
      (node (ref "IC4") (pin "1") (pinfunction "DIR_1") (pintype "input"))
      (node (ref "IC5") (pin "1") (pinfunction "DIR_1") (pintype "input"))
      (node (ref "R19") (pin "2") (pinfunction "2_2") (pintype "passive"))
      (node (ref "SIMM") (pin "47") (pinfunction "47_47") (pintype "passive"))
    )
    (net (code "153") (name "/~{SIMM-WE}") (class "Default")
      (node (ref "GLUE") (pin "57") (pinfunction "IO88_57") (pintype "bidirectional"))
      (node (ref "R19") (pin "1") (pinfunction "1_1") (pintype "passive"))
    )
    (net (code "154") (name "GND") (class "Default")
      (node (ref "BUS") (pin "6") (pinfunction "6_6") (pintype "passive"))
      (node (ref "BUS") (pin "8") (pinfunction "8_8") (pintype "passive"))
      (node (ref "C1") (pin "2") (pinfunction "2_2") (pintype "passive"))
      (node (ref "C17") (pin "-") (pinfunction "-_-") (pintype "passive"))
      (node (ref "C2") (pin "2") (pinfunction "2_2") (pintype "passive"))
      (node (ref "C3") (pin "2") (pinfunction "2_2") (pintype "passive"))
      (node (ref "C4") (pin "2") (pinfunction "2_2") (pintype "passive"))
      (node (ref "C5") (pin "2") (pinfunction "2_2") (pintype "passive"))
      (node (ref "C6") (pin "2") (pinfunction "2_2") (pintype "passive"))
      (node (ref "C7") (pin "2") (pinfunction "2_2") (pintype "passive"))
      (node (ref "C8") (pin "2") (pinfunction "2_2") (pintype "passive"))
      (node (ref "C9") (pin "-") (pinfunction "-_-") (pintype "passive"))
      (node (ref "CTRL") (pin "2") (pinfunction "2_2") (pintype "passive"))
      (node (ref "CTRL") (pin "3") (pinfunction "3_3") (pintype "passive"))
      (node (ref "D-LO") (pin "2") (pinfunction "2_2") (pintype "passive"))
      (node (ref "D-LO") (pin "38") (pinfunction "38_38") (pintype "passive"))
      (node (ref "D-LO") (pin "4") (pinfunction "4_4") (pintype "passive"))
      (node (ref "D-LO") (pin "40") (pinfunction "40_40") (pintype "passive"))
      (node (ref "GCLK2") (pin "3") (pinfunction "3_3") (pintype "passive"))
      (node (ref "GLUE") (pin "19") (pinfunction "GND_19") (pintype "power_in"))
      (node (ref "GLUE") (pin "32") (pinfunction "GND_32") (pintype "power_in"))
      (node (ref "GLUE") (pin "42") (pinfunction "GND_42") (pintype "power_in"))
      (node (ref "GLUE") (pin "47") (pinfunction "GND_47") (pintype "power_in"))
      (node (ref "GLUE") (pin "59") (pinfunction "GND_59") (pintype "power_in"))
      (node (ref "GLUE") (pin "7") (pinfunction "GND_7") (pintype "power_in"))
      (node (ref "GLUE") (pin "72") (pinfunction "GND_72") (pintype "power_in"))
      (node (ref "GLUE") (pin "82") (pinfunction "GND_82") (pintype "power_in"))
      (node (ref "IO11") (pin "3") (pinfunction "3_3") (pintype "passive"))
      (node (ref "IO13") (pin "3") (pinfunction "3_3") (pintype "passive"))
      (node (ref "IO5") (pin "3") (pinfunction "3_3") (pintype "passive"))
      (node (ref "IO6") (pin "3") (pinfunction "3_3") (pintype "passive"))
      (node (ref "IO8") (pin "3") (pinfunction "3_3") (pintype "passive"))
      (node (ref "OE1") (pin "3") (pinfunction "3_3") (pintype "passive"))
      (node (ref "POWER") (pin "2") (pinfunction "S_2") (pintype "passive"))
      (node (ref "POWER") (pin "3") (pinfunction "S_3") (pintype "passive"))
      (node (ref "SIMM") (pin "1") (pinfunction "1_1") (pintype "passive"))
      (node (ref "SIMM") (pin "39") (pinfunction "39_39") (pintype "passive"))
      (node (ref "SIMM") (pin "72") (pinfunction "72_72") (pintype "passive"))
    )
    (net (code "155") (name "VCC") (class "Default")
      (node (ref "BUS") (pin "2") (pinfunction "2_2") (pintype "passive"))
      (node (ref "BUS") (pin "4") (pinfunction "4_4") (pintype "passive"))
      (node (ref "C1") (pin "1") (pinfunction "1_1") (pintype "passive"))
      (node (ref "C17") (pin "+") (pinfunction "+_+") (pintype "passive"))
      (node (ref "C2") (pin "1") (pinfunction "1_1") (pintype "passive"))
      (node (ref "C3") (pin "1") (pinfunction "1_1") (pintype "passive"))
      (node (ref "C4") (pin "1") (pinfunction "1_1") (pintype "passive"))
      (node (ref "C5") (pin "1") (pinfunction "1_1") (pintype "passive"))
      (node (ref "C6") (pin "1") (pinfunction "1_1") (pintype "passive"))
      (node (ref "C7") (pin "1") (pinfunction "1_1") (pintype "passive"))
      (node (ref "C8") (pin "1") (pinfunction "1_1") (pintype "passive"))
      (node (ref "C9") (pin "+") (pinfunction "+_+") (pintype "passive"))
      (node (ref "D-LO") (pin "1") (pinfunction "1_1") (pintype "passive"))
      (node (ref "D-LO") (pin "3") (pinfunction "3_3") (pintype "passive"))
      (node (ref "D-LO") (pin "37") (pinfunction "37_37") (pintype "passive"))
      (node (ref "D-LO") (pin "39") (pinfunction "39_39") (pintype "passive"))
      (node (ref "GCLK2") (pin "1") (pinfunction "1_1") (pintype "passive"))
      (node (ref "GLUE") (pin "13") (pinfunction "VCCIO_13") (pintype "power_in"))
      (node (ref "GLUE") (pin "26") (pinfunction "VCCIO_26") (pintype "power_in"))
      (node (ref "GLUE") (pin "3") (pinfunction "VCC_3") (pintype "power_in"))
      (node (ref "GLUE") (pin "38") (pinfunction "VCCIO_38") (pintype "power_in"))
      (node (ref "GLUE") (pin "43") (pinfunction "VCC_43") (pintype "power_in"))
      (node (ref "GLUE") (pin "53") (pinfunction "VCCIO_53") (pintype "power_in"))
      (node (ref "GLUE") (pin "66") (pinfunction "VCCIO_66") (pintype "power_in"))
      (node (ref "GLUE") (pin "78") (pinfunction "VCCIO_78") (pintype "power_in"))
      (node (ref "IO11") (pin "1") (pinfunction "1_1") (pintype "passive"))
      (node (ref "IO13") (pin "1") (pinfunction "1_1") (pintype "passive"))
      (node (ref "IO5") (pin "1") (pinfunction "1_1") (pintype "passive"))
      (node (ref "IO6") (pin "1") (pinfunction "1_1") (pintype "passive"))
      (node (ref "IO8") (pin "1") (pinfunction "1_1") (pintype "passive"))
      (node (ref "OE1") (pin "1") (pinfunction "1_1") (pintype "passive"))
      (node (ref "POWER") (pin "4") (pinfunction "S_4") (pintype "passive"))
      (node (ref "SIMM") (pin "10") (pinfunction "10_10") (pintype "passive"))
      (node (ref "SIMM") (pin "30") (pinfunction "30_30") (pintype "passive"))
      (node (ref "SIMM") (pin "59") (pinfunction "59_59") (pintype "passive"))
    )
    (net (code "156") (name "unconnected-(D-LO-Pad5)") (class "Default")
      (node (ref "D-LO") (pin "5") (pinfunction "5_5") (pintype "passive"))
    )
    (net (code "157") (name "unconnected-(D-LO-Pad7)") (class "Default")
      (node (ref "D-LO") (pin "7") (pinfunction "7_7") (pintype "passive"))
    )
    (net (code "158") (name "unconnected-(D-LO-Pad9)") (class "Default")
      (node (ref "D-LO") (pin "9") (pinfunction "9_9") (pintype "passive"))
    )
    (net (code "159") (name "unconnected-(D-LO-Pad11)") (class "Default")
      (node (ref "D-LO") (pin "11") (pinfunction "11_11") (pintype "passive"))
    )
    (net (code "160") (name "unconnected-(D-LO-Pad13)") (class "Default")
      (node (ref "D-LO") (pin "13") (pinfunction "13_13") (pintype "passive"))
    )
    (net (code "161") (name "unconnected-(D-LO-Pad15)") (class "Default")
      (node (ref "D-LO") (pin "15") (pinfunction "15_15") (pintype "passive"))
    )
    (net (code "162") (name "unconnected-(D-LO-Pad17)") (class "Default")
      (node (ref "D-LO") (pin "17") (pinfunction "17_17") (pintype "passive"))
    )
    (net (code "163") (name "unconnected-(D-LO-Pad19)") (class "Default")
      (node (ref "D-LO") (pin "19") (pinfunction "19_19") (pintype "passive"))
    )
    (net (code "164") (name "unconnected-(D-LO-Pad21)") (class "Default")
      (node (ref "D-LO") (pin "21") (pinfunction "21_21") (pintype "passive"))
    )
    (net (code "165") (name "unconnected-(D-LO-Pad23)") (class "Default")
      (node (ref "D-LO") (pin "23") (pinfunction "23_23") (pintype "passive"))
    )
    (net (code "166") (name "unconnected-(D-LO-Pad25)") (class "Default")
      (node (ref "D-LO") (pin "25") (pinfunction "25_25") (pintype "passive"))
    )
    (net (code "167") (name "unconnected-(D-LO-Pad27)") (class "Default")
      (node (ref "D-LO") (pin "27") (pinfunction "27_27") (pintype "passive"))
    )
    (net (code "168") (name "unconnected-(D-LO-Pad29)") (class "Default")
      (node (ref "D-LO") (pin "29") (pinfunction "29_29") (pintype "passive"))
    )
    (net (code "169") (name "unconnected-(D-LO-Pad31)") (class "Default")
      (node (ref "D-LO") (pin "31") (pinfunction "31_31") (pintype "passive"))
    )
    (net (code "170") (name "unconnected-(D-LO-Pad33)") (class "Default")
      (node (ref "D-LO") (pin "33") (pinfunction "33_33") (pintype "passive"))
    )
    (net (code "171") (name "unconnected-(D-LO-Pad35)") (class "Default")
      (node (ref "D-LO") (pin "35") (pinfunction "35_35") (pintype "passive"))
    )
    (net (code "172") (name "unconnected-(SIMM-Pad11)") (class "Default")
      (node (ref "SIMM") (pin "11") (pinfunction "11_11") (pintype "passive"))
    )
    (net (code "173") (name "unconnected-(SIMM-Pad35)") (class "Default")
      (node (ref "SIMM") (pin "35") (pinfunction "35_35") (pintype "passive"))
    )
    (net (code "174") (name "unconnected-(SIMM-Pad36)") (class "Default")
      (node (ref "SIMM") (pin "36") (pinfunction "36_36") (pintype "passive"))
    )
    (net (code "175") (name "unconnected-(SIMM-Pad37)") (class "Default")
      (node (ref "SIMM") (pin "37") (pinfunction "37_37") (pintype "passive"))
    )
    (net (code "176") (name "unconnected-(SIMM-Pad38)") (class "Default")
      (node (ref "SIMM") (pin "38") (pinfunction "38_38") (pintype "passive"))
    )
    (net (code "177") (name "unconnected-(SIMM-Pad46)") (class "Default")
      (node (ref "SIMM") (pin "46") (pinfunction "46_46") (pintype "passive"))
    )
    (net (code "178") (name "unconnected-(SIMM-Pad48)") (class "Default")
      (node (ref "SIMM") (pin "48") (pinfunction "48_48") (pintype "passive"))
    )
    (net (code "179") (name "unconnected-(SIMM-Pad66)") (class "Default")
      (node (ref "SIMM") (pin "66") (pinfunction "66_66") (pintype "passive"))
    )
    (net (code "180") (name "unconnected-(SIMM-Pad67)") (class "Default")
      (node (ref "SIMM") (pin "67") (pinfunction "67_67") (pintype "passive"))
    )
    (net (code "181") (name "unconnected-(SIMM-Pad68)") (class "Default")
      (node (ref "SIMM") (pin "68") (pinfunction "68_68") (pintype "passive"))
    )
    (net (code "182") (name "unconnected-(SIMM-Pad69)") (class "Default")
      (node (ref "SIMM") (pin "69") (pinfunction "69_69") (pintype "passive"))
    )
    (net (code "183") (name "unconnected-(SIMM-Pad70)") (class "Default")
      (node (ref "SIMM") (pin "70") (pinfunction "70_70") (pintype "passive"))
    )
    (net (code "184") (name "unconnected-(SIMM-Pad71)") (class "Default")
      (node (ref "SIMM") (pin "71") (pinfunction "71_71") (pintype "passive"))
    )
  )
)
